# gps_blk.net
KiCad netlist of a schematic drawn in Altium Designer
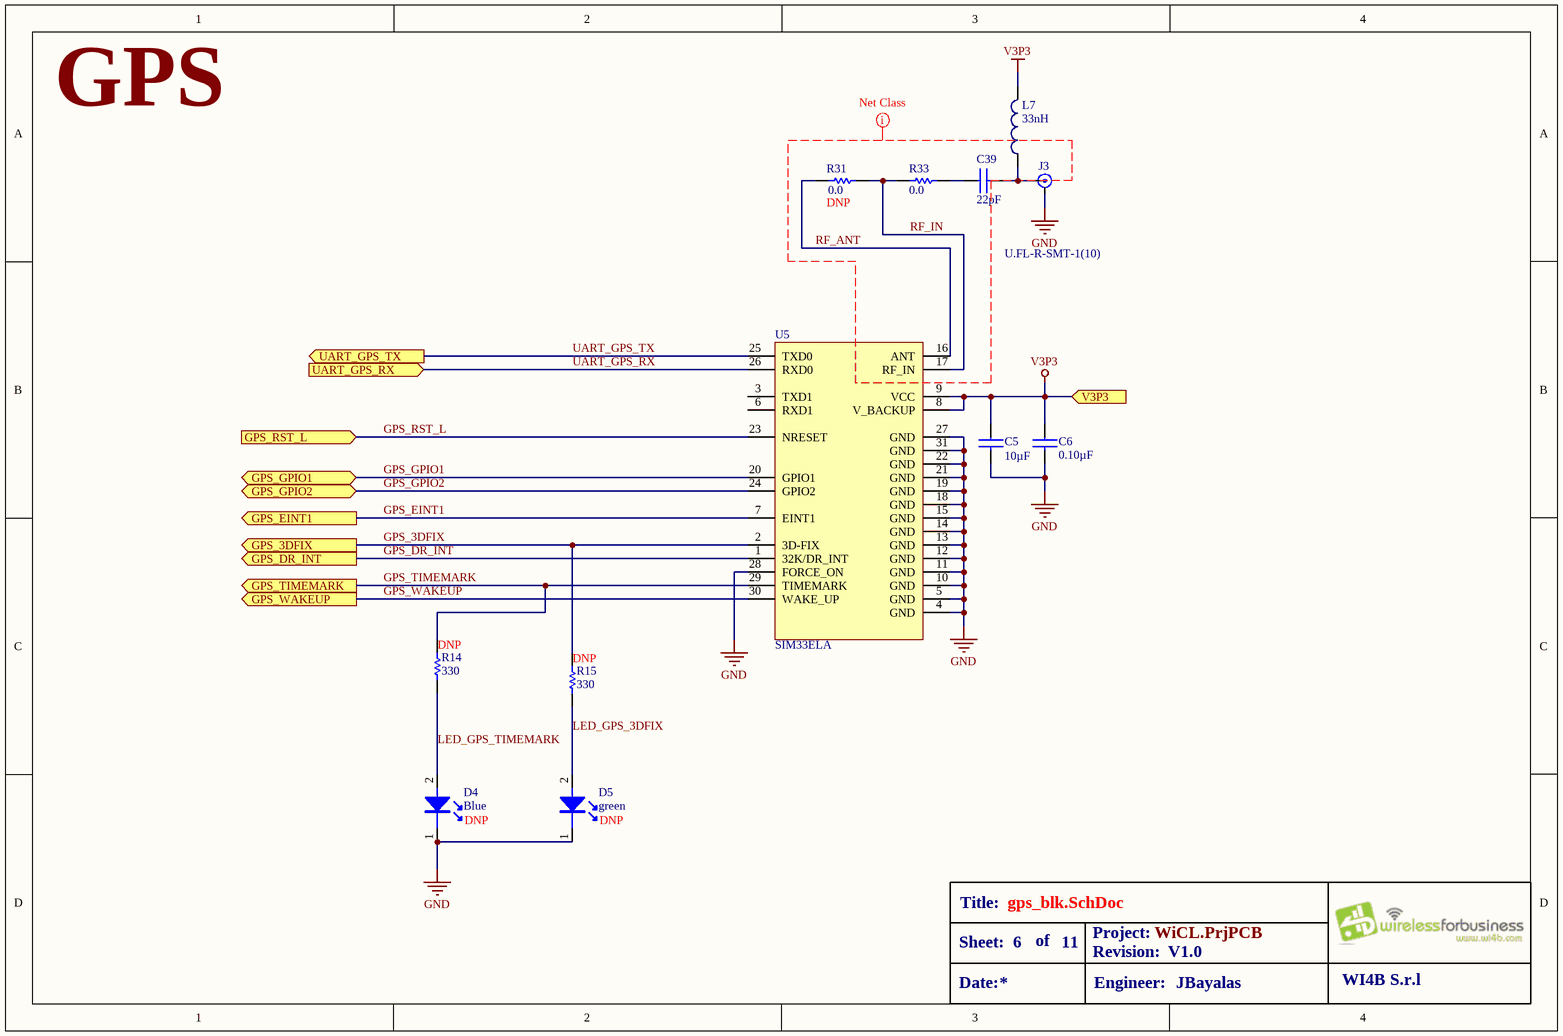
[diagram p0: gps_blk.SchDoc]

(export (version "E")
  (design (tool "Eeschema 10.0.6"))
  (components
    (comp (ref "C5")
      (value "10µF")
      (footprint "C1206")
      (description "CAP CER 10UF 16V X7R 1206")
      (fields (field (name "MPN") "GRM31CR71C106KAC7L"))
      (libsource (lib "Capacitor") (part "GRM31CR71C106KAC7L"))
    )
    (comp (ref "C6")
      (value "0.10µF")
      (footprint "C0402")
      (description "CAP CER 0.1UF 50V X7R 0402")
      (fields (field (name "MPN") "GRM155R71H104ME14D"))
      (libsource (lib "Capacitor") (part "GRM155R71H104ME14D"))
    )
    (comp (ref "C39")
      (value "22pF")
      (footprint "C0402")
      (description "CAP CER 22PF 50V NP0 0402")
      (fields (field (name "MPN") "GRM1555C1H220JA01J"))
      (libsource (lib "Capacitor") (part "GRM1555C1H220JA01J"))
    )
    (comp (ref "D4")
      (value "Blue")
      (footprint "LED0402(BLUE)")
      (description "LED BLUE 0402 SMD")
      (fields (field (name "MPN") "VLMB1500-GS08") (field (name "LOAD") "DNP"))
      (libsource (lib "Diode") (part "VLMB1500-GS08"))
    )
    (comp (ref "D5")
      (value "green")
      (footprint "LED0402(GREEN)")
      (description "LED GREEN CLEAR CHIP SMD")
      (fields (field (name "MPN") "XZVG68W-2") (field (name "LOAD") "DNP"))
      (libsource (lib "Diode") (part "XZVG68W-2"))
    )
    (comp (ref "J3")
      (value "U.FL-R-SMT-1(10)")
      (footprint "U.FL-R-SMT-1(10)")
      (description "CONN UMC JACK STR 50 OHM SMD")
      (fields (field (name "MPN") "U.FL-R-SMT-1(10)"))
      (libsource (lib "EVO_MainBoard_v1.0 ") (part "U.FL-R-SMT-1(10)"))
    )
    (comp (ref "L7")
      (value "33nH")
      (footprint "0603 INDUCTOR")
      (description "FIXED IND 33NH 100MA 2.8 OHM SMD")
      (fields (field (name "MPN") "LQP18MN33NG02D"))
      (libsource (lib "Gateway") (part "LQP18MN33NG02D"))
    )
    (comp (ref "R14")
      (value "330")
      (footprint "R0402")
      (description "RES SMD 330 OHM 1% 1/16W 0402")
      (fields (field (name "MPN") "CRCW0402330RFKED") (field (name "DNP") "DNP"))
      (libsource (lib "Res") (part "CRCW0402330RFKED"))
    )
    (comp (ref "R15")
      (value "330")
      (footprint "R0402")
      (description "RES SMD 330 OHM 1% 1/16W 0402")
      (fields (field (name "MPN") "CRCW0402330RFKED") (field (name "DNP") "DNP"))
      (libsource (lib "Res") (part "CRCW0402330RFKED"))
    )
    (comp (ref "R31")
      (value "0.0")
      (footprint "R0402")
      (description "RES SMD 0.0OHM JUMPER 1/10W 0402")
      (fields (field (name "MPN") "MCS04020Z0000ZE000") (field (name "LOAD") "DNP"))
      (libsource (lib "Res") (part "MCS04020Z0000ZE000"))
    )
    (comp (ref "R33")
      (value "0.0")
      (footprint "R0402")
      (description "RES SMD 0.0OHM JUMPER 1/10W 0402")
      (fields (field (name "MPN") "MCS04020Z0000ZE000"))
      (libsource (lib "Res") (part "MCS04020Z0000ZE000"))
    )
    (comp (ref "U5")
      (value "SIM33ELA")
      (footprint "SIM33ELA")
      (description "A-GPS receiver, with built-in Antenna")
      (fields (field (name "MPN") "SIM33ELA"))
      (libsource (lib "WiLamp_DBoard") (part "SIM33ELA"))
    )
  )
  (nets
    (net (code "1") (name "/GPS_3DFIX") (class "Default")
      (node (ref "R15") (pin "2") (pinfunction "2_2") (pintype "passive"))
      (node (ref "U5") (pin "2") (pinfunction "3D-FIX_2") (pintype "passive"))
    )
    (net (code "2") (name "/GPS_DR_INT") (class "Default")
      (node (ref "U5") (pin "1") (pinfunction "32K/DR_INT_1") (pintype "passive"))
    )
    (net (code "3") (name "/GPS_EINT1") (class "Default")
      (node (ref "U5") (pin "7") (pinfunction "EINT1_7") (pintype "passive"))
    )
    (net (code "4") (name "/GPS_GPIO1") (class "Default")
      (node (ref "U5") (pin "20") (pinfunction "GPIO1_20") (pintype "passive"))
    )
    (net (code "5") (name "/GPS_GPIO2") (class "Default")
      (node (ref "U5") (pin "24") (pinfunction "GPIO2_24") (pintype "passive"))
    )
    (net (code "6") (name "/GPS_RST_L") (class "Default")
      (node (ref "U5") (pin "23") (pinfunction "NRESET_23") (pintype "passive"))
    )
    (net (code "7") (name "/GPS_TIMEMARK") (class "Default")
      (node (ref "R14") (pin "2") (pinfunction "2_2") (pintype "passive"))
      (node (ref "U5") (pin "29") (pinfunction "TIMEMARK_29") (pintype "passive"))
    )
    (net (code "8") (name "/GPS_WAKEUP") (class "Default")
      (node (ref "U5") (pin "30") (pinfunction "WAKE_UP_30") (pintype "passive"))
    )
    (net (code "9") (name "/LED_GPS_3DFIX") (class "Default")
      (node (ref "D5") (pin "2") (pinfunction "2_2") (pintype "passive"))
      (node (ref "R15") (pin "1") (pinfunction "1_1") (pintype "passive"))
    )
    (net (code "10") (name "/LED_GPS_TIMEMARK") (class "Default")
      (node (ref "D4") (pin "2") (pinfunction "2_2") (pintype "passive"))
      (node (ref "R14") (pin "1") (pinfunction "1_1") (pintype "passive"))
    )
    (net (code "11") (name "/RF_ANT") (class "Default")
      (node (ref "R31") (pin "1") (pinfunction "1_1") (pintype "passive"))
      (node (ref "U5") (pin "16") (pinfunction "ANT_16") (pintype "passive"))
    )
    (net (code "12") (name "/RF_IN") (class "Default")
      (node (ref "R31") (pin "2") (pinfunction "2_2") (pintype "passive"))
      (node (ref "R33") (pin "1") (pinfunction "1_1") (pintype "passive"))
      (node (ref "U5") (pin "17") (pinfunction "RF_IN_17") (pintype "passive"))
    )
    (net (code "13") (name "/UART_GPS_RX") (class "Default")
      (node (ref "U5") (pin "26") (pinfunction "RXD0_26") (pintype "passive"))
    )
    (net (code "14") (name "/UART_GPS_TX") (class "Default")
      (node (ref "U5") (pin "25") (pinfunction "TXD0_25") (pintype "passive"))
    )
    (net (code "15") (name "GND") (class "Default")
      (node (ref "C5") (pin "2") (pinfunction "2_2") (pintype "passive"))
      (node (ref "C6") (pin "2") (pinfunction "2_2") (pintype "passive"))
      (node (ref "D4") (pin "1") (pinfunction "1_1") (pintype "passive"))
      (node (ref "D5") (pin "1") (pinfunction "1_1") (pintype "passive"))
      (node (ref "J3") (pin "2") (pinfunction "GND_2") (pintype "passive"))
      (node (ref "U5") (pin "10") (pinfunction "GND_10") (pintype "passive"))
      (node (ref "U5") (pin "11") (pinfunction "GND_11") (pintype "passive"))
      (node (ref "U5") (pin "12") (pinfunction "GND_12") (pintype "passive"))
      (node (ref "U5") (pin "13") (pinfunction "GND_13") (pintype "passive"))
      (node (ref "U5") (pin "14") (pinfunction "GND_14") (pintype "passive"))
      (node (ref "U5") (pin "15") (pinfunction "GND_15") (pintype "passive"))
      (node (ref "U5") (pin "18") (pinfunction "GND_18") (pintype "passive"))
      (node (ref "U5") (pin "19") (pinfunction "GND_19") (pintype "passive"))
      (node (ref "U5") (pin "21") (pinfunction "GND_21") (pintype "passive"))
      (node (ref "U5") (pin "22") (pinfunction "GND_22") (pintype "passive"))
      (node (ref "U5") (pin "27") (pinfunction "GND_27") (pintype "passive"))
      (node (ref "U5") (pin "28") (pinfunction "FORCE_ON_28") (pintype "passive"))
      (node (ref "U5") (pin "31") (pinfunction "GND_31") (pintype "passive"))
      (node (ref "U5") (pin "4") (pinfunction "GND_4") (pintype "passive"))
      (node (ref "U5") (pin "5") (pinfunction "GND_5") (pintype "passive"))
    )
    (net (code "16") (name "Net-(C39-Pad1)") (class "Default")
      (node (ref "C39") (pin "1") (pinfunction "1_1") (pintype "passive"))
      (node (ref "R33") (pin "2") (pinfunction "2_2") (pintype "passive"))
    )
    (net (code "17") (name "Net-(J3-SIGNAL)") (class "Default")
      (node (ref "C39") (pin "2") (pinfunction "2_2") (pintype "passive"))
      (node (ref "J3") (pin "1") (pinfunction "SIGNAL_1") (pintype "passive"))
      (node (ref "L7") (pin "2") (pinfunction "2_2") (pintype "passive"))
    )
    (net (code "18") (name "V3P3") (class "Default")
      (node (ref "C5") (pin "1") (pinfunction "1_1") (pintype "passive"))
      (node (ref "C6") (pin "1") (pinfunction "1_1") (pintype "passive"))
      (node (ref "L7") (pin "1") (pinfunction "1_1") (pintype "passive"))
      (node (ref "U5") (pin "8") (pinfunction "V_BACKUP_8") (pintype "passive"))
      (node (ref "U5") (pin "9") (pinfunction "VCC_9") (pintype "passive"))
    )
    (net (code "19") (name "unconnected-(U5-RXD1-Pad6)") (class "Default")
      (node (ref "U5") (pin "6") (pinfunction "RXD1_6") (pintype "passive"))
    )
    (net (code "20") (name "unconnected-(U5-TXD1-Pad3)") (class "Default")
      (node (ref "U5") (pin "3") (pinfunction "TXD1_3") (pintype "passive"))
    )
  )
)
